# Target_Control_System_Front_Panel.net
KiCad netlist of a schematic drawn in Altium Designer
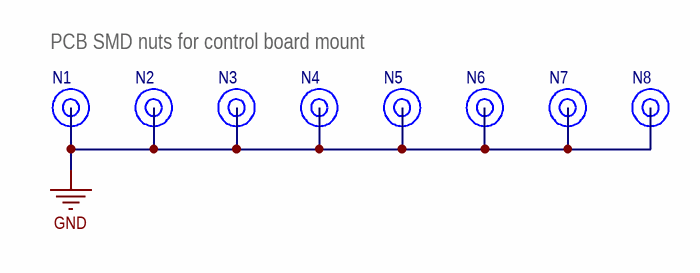
[diagram p0: Target Control System Front Panel.SchDoc]

(export (version "E")
  (design (tool "Eeschema 10.0.6"))
  (components
    (comp (ref "N1")
      (value "PCB Nut")
      (footprint "PCB Nut M3 SMD")
      (description "SMD or through hole soldered PCB nut")
      (libsource (lib "Peake Electronic Innovation") (part "PCB Nut-Symbol-1"))
    )
    (comp (ref "N2")
      (value "PCB Nut")
      (footprint "PCB Nut M3 SMD")
      (description "SMD or through hole soldered PCB nut")
      (libsource (lib "Peake Electronic Innovation") (part "PCB Nut-Symbol-1"))
    )
    (comp (ref "N3")
      (value "PCB Nut")
      (footprint "PCB Nut M3 SMD")
      (description "SMD or through hole soldered PCB nut")
      (libsource (lib "Peake Electronic Innovation") (part "PCB Nut-Symbol-1"))
    )
    (comp (ref "N4")
      (value "PCB Nut")
      (footprint "PCB Nut M3 SMD")
      (description "SMD or through hole soldered PCB nut")
      (libsource (lib "Peake Electronic Innovation") (part "PCB Nut-Symbol-1"))
    )
    (comp (ref "N5")
      (value "PCB Nut")
      (footprint "PCB Nut M3 SMD")
      (description "SMD or through hole soldered PCB nut")
      (libsource (lib "Peake Electronic Innovation") (part "PCB Nut-Symbol-1"))
    )
    (comp (ref "N6")
      (value "PCB Nut")
      (footprint "PCB Nut M3 SMD")
      (description "SMD or through hole soldered PCB nut")
      (libsource (lib "Peake Electronic Innovation") (part "PCB Nut-Symbol-1"))
    )
    (comp (ref "N7")
      (value "PCB Nut")
      (footprint "PCB Nut M3 SMD")
      (description "SMD or through hole soldered PCB nut")
      (libsource (lib "Peake Electronic Innovation") (part "PCB Nut-Symbol-1"))
    )
    (comp (ref "N8")
      (value "PCB Nut")
      (footprint "PCB Nut M3 SMD")
      (description "SMD or through hole soldered PCB nut")
      (libsource (lib "Peake Electronic Innovation") (part "PCB Nut-Symbol-1"))
    )
  )
  (nets
    (net (code "1") (name "GND") (class "Default")
      (node (ref "N1") (pin "1") (pintype "passive"))
      (node (ref "N2") (pin "1") (pintype "passive"))
      (node (ref "N3") (pin "1") (pintype "passive"))
      (node (ref "N4") (pin "1") (pintype "passive"))
      (node (ref "N5") (pin "1") (pintype "passive"))
      (node (ref "N6") (pin "1") (pintype "passive"))
      (node (ref "N7") (pin "1") (pintype "passive"))
      (node (ref "N8") (pin "1") (pintype "passive"))
    )
  )
)
